# Output_amplifier.net
KiCad netlist of a schematic drawn in Altium Designer
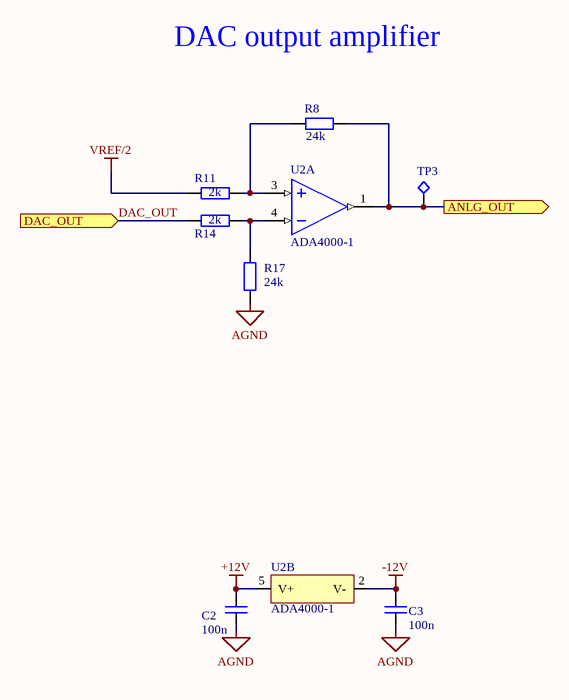
[diagram p0: Output_amplifier.SchDoc]

(export (version "E")
  (design (tool "Eeschema 10.0.6"))
  (components
    (comp (ref "C2")
      (value "100n")
      (footprint "C_0603")
      (description "Generic capacitor")
      (libsource (lib "DAQ") (part "Capacitor"))
    )
    (comp (ref "C3")
      (value "100n")
      (footprint "C_0603")
      (description "Generic capacitor")
      (libsource (lib "DAQ") (part "Capacitor"))
    )
    (comp (ref "R8")
      (value "24k")
      (footprint "R_0603")
      (description "Generic resistor")
      (fields (field (name "Comment") "comment"))
      (libsource (lib "DAQ") (part "Resistor"))
    )
    (comp (ref "R11")
      (value "2k")
      (footprint "R_0603")
      (description "Generic resistor")
      (fields (field (name "Comment") "comment"))
      (libsource (lib "DAQ") (part "Resistor"))
    )
    (comp (ref "R14")
      (value "2k")
      (footprint "R_0603")
      (description "Generic resistor")
      (fields (field (name "Comment") "comment"))
      (libsource (lib "DAQ") (part "Resistor"))
    )
    (comp (ref "R17")
      (value "24k")
      (footprint "R_0603")
      (description "Generic resistor")
      (fields (field (name "Comment") "comment"))
      (libsource (lib "DAQ") (part "Resistor"))
    )
    (comp (ref "TP3")
      (value "testpoint")
      (footprint "TP1_FULL")
      (description "testpoint 1.5mm diameter no hole")
      (fields (field (name "PART NUMBER") "XXC0006"))
      (libsource (lib "DAQ") (part "Test Point"))
    )
    (comp (ref "U2")
      (value "ADA4000-1")
      (footprint "SOT23-5")
      (description "Operational Amplifier, Single, 1 Amplifier, 5 MHz, 20 V/µs, ± 4V to ± 18V, TSOT, 5 Pins")
      (fields (field (name "PART NUMBER") "XOG0003") (field (name "MANUFACTURER") "Analog devices"))
      (libsource (lib "DAQ") (part "ADA4000-1"))
    )
  )
  (nets
    (net (code "1") (name "+12V") (class "Default")
      (node (ref "C2") (pin "1") (pinfunction "1_1") (pintype "passive"))
      (node (ref "U2") (pin "5") (pinfunction "V+_5") (pintype "power_in"))
    )
    (net (code "2") (name "-12V") (class "Default")
      (node (ref "C3") (pin "1") (pinfunction "1_1") (pintype "passive"))
      (node (ref "U2") (pin "2") (pinfunction "V-_2") (pintype "power_in"))
    )
    (net (code "3") (name "/ANLG_OUT") (class "Default")
      (node (ref "R8") (pin "2") (pintype "passive"))
      (node (ref "TP3") (pin "1") (pinfunction "1_1") (pintype "passive"))
      (node (ref "U2") (pin "1") (pinfunction "OUT_1") (pintype "output"))
    )
    (net (code "4") (name "/DAC_OUT") (class "Default") (node (ref "R14") (pin "1") (pintype "passive")))
    (net (code "5") (name "AGND") (class "Default")
      (node (ref "C2") (pin "2") (pinfunction "2_2") (pintype "passive"))
      (node (ref "C3") (pin "2") (pinfunction "2_2") (pintype "passive"))
      (node (ref "R17") (pin "1") (pintype "passive"))
    )
    (net (code "6") (name "Net-(U2A-IN+)") (class "Default")
      (node (ref "R11") (pin "2") (pintype "passive"))
      (node (ref "R8") (pin "1") (pintype "passive"))
      (node (ref "U2") (pin "3") (pinfunction "IN+_3") (pintype "input"))
    )
    (net (code "7") (name "Net-(U2A-IN-)") (class "Default")
      (node (ref "R14") (pin "2") (pintype "passive"))
      (node (ref "R17") (pin "2") (pintype "passive"))
      (node (ref "U2") (pin "4") (pinfunction "IN-_4") (pintype "input"))
    )
    (net (code "8") (name "VREF{slash}2") (class "Default") (node (ref "R11") (pin "1") (pintype "passive")))
  )
)
